# Sheet1.net
KiCad netlist of a schematic drawn in Altium Designer
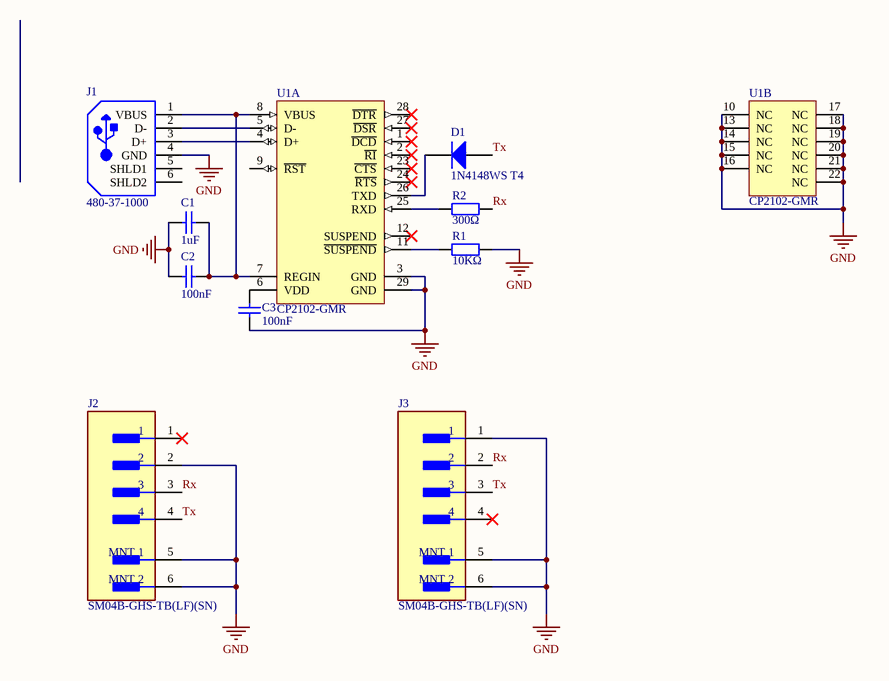
[diagram p0: Sheet1.SchDoc]

(export (version "E")
  (design (tool "Eeschema 10.0.6"))
  (components
    (comp (ref "C1")
      (value "1uF")
      (footprint "0603_C")
      (description "贴片电容, 1uF (105) 10% 50V")
      (libsource (lib "Miscellaneous Devices LC") (part "0603 1uF (105) 10% 50V"))
    )
    (comp (ref "C2")
      (value "100nF")
      (footprint "0402_C")
      (description "贴片电容, 100nF (104) 10% 16V")
      (libsource (lib "Miscellaneous Devices LC") (part "0402 100nF (104) 10% 16V"))
    )
    (comp (ref "C3")
      (value "100nF")
      (footprint "0402_C")
      (description "贴片电容, 100nF (104) 10% 16V")
      (libsource (lib "Miscellaneous Devices LC") (part "0402 100nF (104) 10% 16V"))
    )
    (comp (ref "D1")
      (value "1N4148WS T4")
      (footprint "SOD-323")
      (description "二极管")
      (libsource (lib "Miscellaneous Devices LC") (part "SOD-323 1N4148WS T4"))
    )
    (comp (ref "J1")
      (value "480-37-1000")
      (footprint "MOLX-480-37-1000_V")
      (fields (field (name "TOLERANCE") "1%"))
      (libsource (lib "Altium Content Vault") (part "USB-4-2SHLD"))
    )
    (comp (ref "J2")
      (value "SM04B-GHS-TB(LF)(SN)")
      (footprint "FP-SM04B-GHS-TB_LF_SN-MFG")
      (description "CONN HEADER SMD R/A 4POS 1.25MM")
      (libsource (lib "Altium Content Vault") (part "f4320a1371cd6270e33bce1916c33c0"))
    )
    (comp (ref "J3")
      (value "SM04B-GHS-TB(LF)(SN)")
      (footprint "FP-SM04B-GHS-TB_LF_SN-MFG")
      (description "CONN HEADER SMD R/A 4POS 1.25MM")
      (libsource (lib "Altium Content Vault") (part "f4320a1371cd6270e33bce1916c33c0"))
    )
    (comp (ref "R1")
      (value "10KΩ")
      (footprint "0402_R")
      (description "贴片电阻, 10KΩ (1002) ±1%")
      (libsource (lib "Miscellaneous Devices LC") (part "0402 10KΩ (1002) 1%"))
    )
    (comp (ref "R2")
      (value "300Ω")
      (footprint "0603_R")
      (description "贴片电阻, 300Ω (3000) ±1%")
      (libsource (lib "Miscellaneous Devices LC") (part "0603 300Ω (3000) 1%"))
    )
    (comp (ref "U1")
      (value "CP2102-GMR")
      (footprint "SLAB-QFN-28-3125x3125TP_M")
      (description "Single-Chip USB to URAT Bridge, 3.3 V, -40 to 85 degC, 28-Pin QFN, RoHS, Tape and Reel")
      (fields (field (name "MANUFACTURER") "Silicon Labs"))
      (libsource (lib "Altium Content Vault") (part "SLAB-CP210X-QFN-28-29"))
    )
  )
  (nets
    (net (code "1") (name "/Rx") (class "Default")
      (node (ref "J2") (pin "3") (pinfunction "3_3") (pintype "passive"))
      (node (ref "J3") (pin "2") (pinfunction "2_2") (pintype "passive"))
      (node (ref "R2") (pin "2") (pinfunction "2_2") (pintype "passive"))
    )
    (net (code "2") (name "/Tx") (class "Default")
      (node (ref "D1") (pin "1") (pinfunction "A_1") (pintype "passive"))
      (node (ref "J2") (pin "4") (pinfunction "4_4") (pintype "passive"))
      (node (ref "J3") (pin "3") (pinfunction "3_3") (pintype "passive"))
    )
    (net (code "3") (name "GND") (class "Default")
      (node (ref "C1") (pin "1") (pinfunction "1_1") (pintype "passive"))
      (node (ref "C2") (pin "1") (pinfunction "1_1") (pintype "passive"))
      (node (ref "C3") (pin "1") (pinfunction "1_1") (pintype "passive"))
      (node (ref "J1") (pin "4") (pinfunction "GND_4") (pintype "passive"))
      (node (ref "J2") (pin "2") (pinfunction "2_2") (pintype "passive"))
      (node (ref "J2") (pin "5") (pinfunction "MNT_1_5") (pintype "passive"))
      (node (ref "J2") (pin "6") (pinfunction "MNT_2_6") (pintype "passive"))
      (node (ref "J3") (pin "1") (pinfunction "1_1") (pintype "passive"))
      (node (ref "J3") (pin "5") (pinfunction "MNT_1_5") (pintype "passive"))
      (node (ref "J3") (pin "6") (pinfunction "MNT_2_6") (pintype "passive"))
      (node (ref "R1") (pin "2") (pinfunction "2_2") (pintype "passive"))
      (node (ref "U1") (pin "10") (pinfunction "NC_10") (pintype "passive"))
      (node (ref "U1") (pin "13") (pinfunction "NC_13") (pintype "passive"))
      (node (ref "U1") (pin "14") (pinfunction "NC_14") (pintype "passive"))
      (node (ref "U1") (pin "15") (pinfunction "NC_15") (pintype "passive"))
      (node (ref "U1") (pin "16") (pinfunction "NC_16") (pintype "passive"))
      (node (ref "U1") (pin "17") (pinfunction "NC_17") (pintype "passive"))
      (node (ref "U1") (pin "18") (pinfunction "NC_18") (pintype "passive"))
      (node (ref "U1") (pin "19") (pinfunction "NC_19") (pintype "passive"))
      (node (ref "U1") (pin "20") (pinfunction "NC_20") (pintype "passive"))
      (node (ref "U1") (pin "21") (pinfunction "NC_21") (pintype "passive"))
      (node (ref "U1") (pin "22") (pinfunction "NC_22") (pintype "passive"))
      (node (ref "U1") (pin "29") (pinfunction "GND_29") (pintype "power_in"))
      (node (ref "U1") (pin "3") (pinfunction "GND_3") (pintype "power_in"))
    )
    (net (code "4") (name "Net-(D1-K)") (class "Default")
      (node (ref "D1") (pin "2") (pinfunction "K_2") (pintype "passive"))
      (node (ref "U1") (pin "26") (pinfunction "TXD_26") (pintype "output"))
    )
    (net (code "5") (name "Net-(J1-D+)") (class "Default")
      (node (ref "J1") (pin "3") (pinfunction "D+_3") (pintype "passive"))
      (node (ref "U1") (pin "4") (pinfunction "D+_4") (pintype "bidirectional"))
    )
    (net (code "6") (name "Net-(J1-D-)") (class "Default")
      (node (ref "J1") (pin "2") (pinfunction "D-_2") (pintype "passive"))
      (node (ref "U1") (pin "5") (pinfunction "D-_5") (pintype "bidirectional"))
    )
    (net (code "7") (name "Net-(J1-VBUS)") (class "Default")
      (node (ref "C1") (pin "2") (pinfunction "2_2") (pintype "passive"))
      (node (ref "C2") (pin "2") (pinfunction "2_2") (pintype "passive"))
      (node (ref "J1") (pin "1") (pinfunction "VBUS_1") (pintype "passive"))
      (node (ref "U1") (pin "7") (pinfunction "REGIN_7") (pintype "power_in"))
      (node (ref "U1") (pin "8") (pinfunction "VBUS_8") (pintype "input"))
    )
    (net (code "8") (name "Net-(U1A-RXD)") (class "Default")
      (node (ref "R2") (pin "1") (pinfunction "1_1") (pintype "passive"))
      (node (ref "U1") (pin "25") (pinfunction "RXD_25") (pintype "input"))
    )
    (net (code "9") (name "Net-(U1A-VDD)") (class "Default")
      (node (ref "C3") (pin "2") (pinfunction "2_2") (pintype "passive"))
      (node (ref "U1") (pin "6") (pinfunction "VDD_6") (pintype "power_in"))
    )
    (net (code "10") (name "Net-(U1A-~{SUSPEND})") (class "Default")
      (node (ref "R1") (pin "1") (pinfunction "1_1") (pintype "passive"))
      (node (ref "U1") (pin "11") (pinfunction "~{SUSPEND}_11") (pintype "output"))
    )
    (net (code "11") (name "unconnected-(J1-SHLD1-Pad5)") (class "Default")
      (node (ref "J1") (pin "5") (pinfunction "SHLD1_5") (pintype "passive"))
    )
    (net (code "12") (name "unconnected-(J1-SHLD2-Pad6)") (class "Default")
      (node (ref "J1") (pin "6") (pinfunction "SHLD2_6") (pintype "passive"))
    )
    (net (code "13") (name "unconnected-(J2-Pad1)") (class "Default")
      (node (ref "J2") (pin "1") (pinfunction "1_1") (pintype "passive+no_connect"))
    )
    (net (code "14") (name "unconnected-(J3-Pad4)") (class "Default")
      (node (ref "J3") (pin "4") (pinfunction "4_4") (pintype "passive+no_connect"))
    )
    (net (code "15") (name "unconnected-(U1A-SUSPEND-Pad12)") (class "Default")
      (node (ref "U1") (pin "12") (pinfunction "SUSPEND_12") (pintype "output+no_connect"))
    )
    (net (code "16") (name "unconnected-(U1A-~{CTS}-Pad23)") (class "Default")
      (node (ref "U1") (pin "23") (pinfunction "~{CTS}_23") (pintype "input+no_connect"))
    )
    (net (code "17") (name "unconnected-(U1A-~{DCD}-Pad1)") (class "Default")
      (node (ref "U1") (pin "1") (pinfunction "~{DCD}_1") (pintype "input+no_connect"))
    )
    (net (code "18") (name "unconnected-(U1A-~{DSR}-Pad27)") (class "Default")
      (node (ref "U1") (pin "27") (pinfunction "~{DSR}_27") (pintype "input+no_connect"))
    )
    (net (code "19") (name "unconnected-(U1A-~{DTR}-Pad28)") (class "Default")
      (node (ref "U1") (pin "28") (pinfunction "~{DTR}_28") (pintype "output+no_connect"))
    )
    (net (code "20") (name "unconnected-(U1A-~{RI}-Pad2)") (class "Default")
      (node (ref "U1") (pin "2") (pinfunction "~{RI}_2") (pintype "input+no_connect"))
    )
    (net (code "21") (name "unconnected-(U1A-~{RST}-Pad9)") (class "Default")
      (node (ref "U1") (pin "9") (pinfunction "~{RST}_9") (pintype "bidirectional"))
    )
    (net (code "22") (name "unconnected-(U1A-~{RTS}-Pad24)") (class "Default")
      (node (ref "U1") (pin "24") (pinfunction "~{RTS}_24") (pintype "output+no_connect"))
    )
  )
)
